# CAN_Address_Switch_Array.net
KiCad netlist of a schematic drawn in Altium Designer
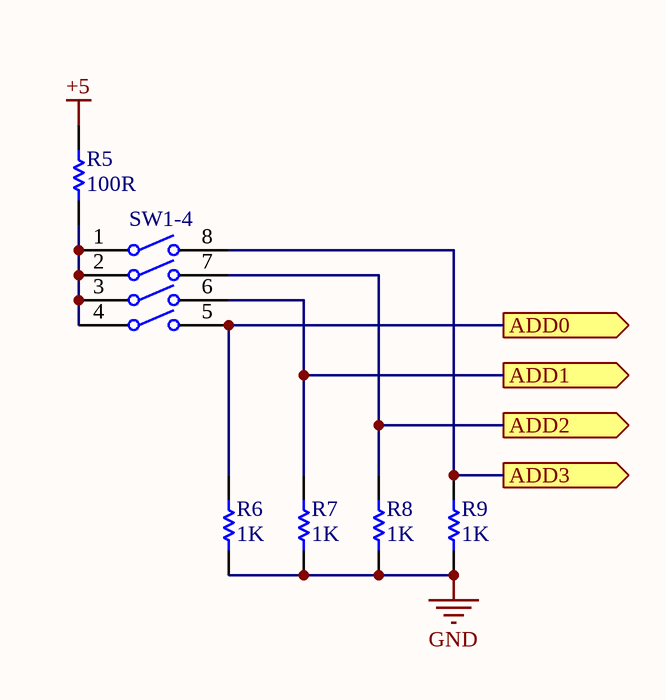
[diagram p0: CAN Address Switch Array.SchDoc]

(export (version "E")
  (design (tool "Eeschema 10.0.6"))
  (components
    (comp (ref "R5")
      (value "100R")
      (footprint "RESC0805(2012)_L")
      (description "100R 0.125W 1% 0805 (2012 Metric)  SMD")
      (fields (field (name "POWER") "0.125 W") (field (name "TOLERANCE") "1 %"))
      (libsource (lib "Altium Content Vault") (part "RES"))
    )
    (comp (ref "R6")
      (value "1K")
      (footprint "RESC0805(2012)_M")
      (description "1K 0.125W 1% 0805 (2012 Metric)  SMD")
      (fields (field (name "TOLERANCE") "1 %") (field (name "POWER") "0.125 W"))
      (libsource (lib "Altium Content Vault") (part "RES"))
    )
    (comp (ref "R7")
      (value "1K")
      (footprint "RESC0805(2012)_M")
      (description "1K 0.125W 1% 0805 (2012 Metric)  SMD")
      (fields (field (name "TOLERANCE") "1 %") (field (name "POWER") "0.125 W"))
      (libsource (lib "Altium Content Vault") (part "RES"))
    )
    (comp (ref "R8")
      (value "1K")
      (footprint "RESC0805(2012)_M")
      (description "1K 0.125W 1% 0805 (2012 Metric)  SMD")
      (fields (field (name "TOLERANCE") "1 %") (field (name "POWER") "0.125 W"))
      (libsource (lib "Altium Content Vault") (part "RES"))
    )
    (comp (ref "R9")
      (value "1K")
      (footprint "RESC0805(2012)_M")
      (description "1K 0.125W 1% 0805 (2012 Metric)  SMD")
      (fields (field (name "TOLERANCE") "1 %") (field (name "POWER") "0.125 W"))
      (libsource (lib "Altium Content Vault") (part "RES"))
    )
    (comp (ref "SW1-4")
      (value "TDA04H0SB1")
      (footprint "CKCP-TDA04H0SB1R_V")
      (libsource (lib "Husky Robotics Standard Library 2019-2020") (part "SMD Half-Pitch Dip Switch Array"))
    )
  )
  (nets
    (net (code "1") (name "+5") (class "Default")
      (node (ref "R5") (pin "2") (pinfunction "2_2") (pintype "passive"))
    )
    (net (code "2") (name "/ADD0") (class "Default")
      (node (ref "R6") (pin "2") (pinfunction "2_2") (pintype "passive"))
      (node (ref "SW1-4") (pin "5") (pinfunction "5_5") (pintype "passive"))
    )
    (net (code "3") (name "/ADD1") (class "Default")
      (node (ref "R7") (pin "2") (pinfunction "2_2") (pintype "passive"))
      (node (ref "SW1-4") (pin "6") (pinfunction "6_6") (pintype "passive"))
    )
    (net (code "4") (name "/ADD2") (class "Default")
      (node (ref "R8") (pin "2") (pinfunction "2_2") (pintype "passive"))
      (node (ref "SW1-4") (pin "7") (pinfunction "7_7") (pintype "passive"))
    )
    (net (code "5") (name "/ADD3") (class "Default")
      (node (ref "R9") (pin "2") (pinfunction "2_2") (pintype "passive"))
      (node (ref "SW1-4") (pin "8") (pinfunction "8_8") (pintype "passive"))
    )
    (net (code "6") (name "GND") (class "Default")
      (node (ref "R6") (pin "1") (pinfunction "1_1") (pintype "passive"))
      (node (ref "R7") (pin "1") (pinfunction "1_1") (pintype "passive"))
      (node (ref "R8") (pin "1") (pinfunction "1_1") (pintype "passive"))
      (node (ref "R9") (pin "1") (pinfunction "1_1") (pintype "passive"))
    )
    (net (code "7") (name "Net-(R5-Pad1)") (class "Default")
      (node (ref "R5") (pin "1") (pinfunction "1_1") (pintype "passive"))
      (node (ref "SW1-4") (pin "1") (pinfunction "1_1") (pintype "passive"))
      (node (ref "SW1-4") (pin "2") (pinfunction "2_2") (pintype "passive"))
      (node (ref "SW1-4") (pin "3") (pinfunction "3_3") (pintype "passive"))
      (node (ref "SW1-4") (pin "4") (pinfunction "4_4") (pintype "passive"))
    )
  )
)
